# SH06-UI.net
KiCad netlist of a schematic drawn in Altium Designer
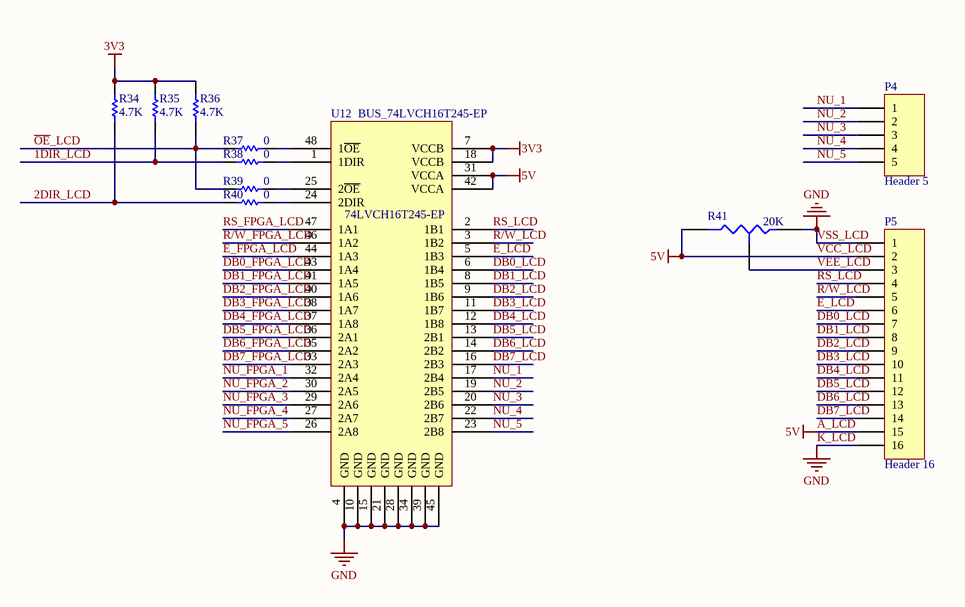
[diagram p0: SH06-UI.SchDoc]

(export (version "E")
  (design (tool "Eeschema 10.0.6"))
  (components
    (comp (ref "P4")
      (value "Header 5")
      (footprint "HDR1X5")
      (description "Header, 5-Pin")
      (fields (field (name "PUBLISHER") "Altium Limited"))
      (libsource (lib "Miscellaneous Connectors") (part "Header 5"))
    )
    (comp (ref "P5")
      (value "Header 16")
      (footprint "HDR1X16")
      (description "Header, 16-Pin")
      (fields (field (name "PUBLISHER") "Altium Limited"))
      (libsource (lib "Miscellaneous Connectors") (part "Header 16"))
    )
    (comp (ref "R34")
      (value "4.7K")
      (footprint "Laser-LiuXin:1608[0603]")
      (description "Resistor")
      (fields (field (name "Comment") "Res,4.7K/0603") (field (name "PUBLISHER") "Altium Limited"))
      (libsource (lib "Miscellaneous Devices") (part "Res1"))
    )
    (comp (ref "R35")
      (value "4.7K")
      (footprint "Laser-LiuXin:1608[0603]")
      (description "Resistor")
      (fields (field (name "Comment") "Res,4.7K/0603") (field (name "PUBLISHER") "Altium Limited"))
      (libsource (lib "Miscellaneous Devices") (part "Res1"))
    )
    (comp (ref "R36")
      (value "4.7K")
      (footprint "Laser-LiuXin:1608[0603]")
      (description "Resistor")
      (fields (field (name "Comment") "Res,4.7K/0603") (field (name "PUBLISHER") "Altium Limited"))
      (libsource (lib "Miscellaneous Devices") (part "Res1"))
    )
    (comp (ref "R37")
      (value "0")
      (footprint "Laser-LiuXin:1608[0603]")
      (description "Resistor")
      (fields (field (name "Comment") "Res,0R/0603") (field (name "PUBLISHER") "Altium Limited"))
      (libsource (lib "Miscellaneous Devices") (part "Res1"))
    )
    (comp (ref "R38")
      (value "0")
      (footprint "Laser-LiuXin:1608[0603]")
      (description "Resistor")
      (fields (field (name "Comment") "Res,0R/0603") (field (name "PUBLISHER") "Altium Limited"))
      (libsource (lib "Miscellaneous Devices") (part "Res1"))
    )
    (comp (ref "R39")
      (value "0")
      (footprint "Laser-LiuXin:1608[0603]")
      (description "Resistor")
      (fields (field (name "Comment") "Res,0R/0603") (field (name "PUBLISHER") "Altium Limited"))
      (libsource (lib "Miscellaneous Devices") (part "Res1"))
    )
    (comp (ref "R40")
      (value "0")
      (footprint "Laser-LiuXin:1608[0603]")
      (description "Resistor")
      (fields (field (name "Comment") "Res,0R/0603") (field (name "PUBLISHER") "Altium Limited"))
      (libsource (lib "Miscellaneous Devices") (part "Res1"))
    )
    (comp (ref "R41")
      (value "20K")
      (footprint "Laser-LiuXin:RES-adj")
      (description "Tapped Resistor")
      (fields (field (name "Comment") "Res Adj,20K") (field (name "PUBLISHER") "Altium Limited"))
      (libsource (lib "Miscellaneous Devices") (part "Res Tap"))
    )
    (comp (ref "U12")
      (value "BUS_74LVCH16T245-EP")
      (footprint "Laser-LiuXin:TSSOP50P810X120-48N")
      (libsource (lib "Laser-LiuXin") (part "BUS_74LVCH16T245-EP"))
    )
  )
  (nets
    (net (code "1") (name "/1DIR_LCD") (class "Default")
      (node (ref "R35") (pin "1") (pinfunction "1_1") (pintype "passive"))
      (node (ref "R38") (pin "1") (pinfunction "1_1") (pintype "passive"))
    )
    (net (code "2") (name "/2DIR_LCD") (class "Default")
      (node (ref "R34") (pin "1") (pinfunction "1_1") (pintype "passive"))
      (node (ref "R40") (pin "1") (pinfunction "1_1") (pintype "passive"))
    )
    (net (code "3") (name "/DB0_FPGA_LCD") (class "Default")
      (node (ref "U12") (pin "43") (pinfunction "1A4_43") (pintype "passive"))
    )
    (net (code "4") (name "/DB0_LCD") (class "Default")
      (node (ref "P5") (pin "7") (pinfunction "7_7") (pintype "passive"))
      (node (ref "U12") (pin "6") (pinfunction "1B4_6") (pintype "passive"))
    )
    (net (code "5") (name "/DB1_FPGA_LCD") (class "Default")
      (node (ref "U12") (pin "41") (pinfunction "1A5_41") (pintype "passive"))
    )
    (net (code "6") (name "/DB1_LCD") (class "Default")
      (node (ref "P5") (pin "8") (pinfunction "8_8") (pintype "passive"))
      (node (ref "U12") (pin "8") (pinfunction "1B5_8") (pintype "passive"))
    )
    (net (code "7") (name "/DB2_FPGA_LCD") (class "Default")
      (node (ref "U12") (pin "40") (pinfunction "1A6_40") (pintype "passive"))
    )
    (net (code "8") (name "/DB2_LCD") (class "Default")
      (node (ref "P5") (pin "9") (pinfunction "9_9") (pintype "passive"))
      (node (ref "U12") (pin "9") (pinfunction "1B6_9") (pintype "passive"))
    )
    (net (code "9") (name "/DB3_FPGA_LCD") (class "Default")
      (node (ref "U12") (pin "38") (pinfunction "1A7_38") (pintype "passive"))
    )
    (net (code "10") (name "/DB3_LCD") (class "Default")
      (node (ref "P5") (pin "10") (pinfunction "10_10") (pintype "passive"))
      (node (ref "U12") (pin "11") (pinfunction "1B7_11") (pintype "passive"))
    )
    (net (code "11") (name "/DB4_FPGA_LCD") (class "Default")
      (node (ref "U12") (pin "37") (pinfunction "1A8_37") (pintype "passive"))
    )
    (net (code "12") (name "/DB4_LCD") (class "Default")
      (node (ref "P5") (pin "11") (pinfunction "11_11") (pintype "passive"))
      (node (ref "U12") (pin "12") (pinfunction "1B8_12") (pintype "passive"))
    )
    (net (code "13") (name "/DB5_FPGA_LCD") (class "Default")
      (node (ref "U12") (pin "36") (pinfunction "2A1_36") (pintype "passive"))
    )
    (net (code "14") (name "/DB5_LCD") (class "Default")
      (node (ref "P5") (pin "12") (pinfunction "12_12") (pintype "passive"))
      (node (ref "U12") (pin "13") (pinfunction "2B1_13") (pintype "passive"))
    )
    (net (code "15") (name "/DB6_FPGA_LCD") (class "Default")
      (node (ref "U12") (pin "35") (pinfunction "2A2_35") (pintype "passive"))
    )
    (net (code "16") (name "/DB6_LCD") (class "Default")
      (node (ref "P5") (pin "13") (pinfunction "13_13") (pintype "passive"))
      (node (ref "U12") (pin "14") (pinfunction "2B2_14") (pintype "passive"))
    )
    (net (code "17") (name "/DB7_FPGA_LCD") (class "Default")
      (node (ref "U12") (pin "33") (pinfunction "2A3_33") (pintype "passive"))
    )
    (net (code "18") (name "/DB7_LCD") (class "Default")
      (node (ref "P5") (pin "14") (pinfunction "14_14") (pintype "passive"))
      (node (ref "U12") (pin "16") (pinfunction "2B3_16") (pintype "passive"))
    )
    (net (code "19") (name "/E_FPGA_LCD") (class "Default")
      (node (ref "U12") (pin "44") (pinfunction "1A3_44") (pintype "passive"))
    )
    (net (code "20") (name "/E_LCD") (class "Default")
      (node (ref "P5") (pin "6") (pinfunction "6_6") (pintype "passive"))
      (node (ref "U12") (pin "5") (pinfunction "1B3_5") (pintype "passive"))
    )
    (net (code "21") (name "/NU_1") (class "Default")
      (node (ref "P4") (pin "1") (pinfunction "1_1") (pintype "passive"))
      (node (ref "U12") (pin "17") (pinfunction "2B4_17") (pintype "passive"))
    )
    (net (code "22") (name "/NU_2") (class "Default")
      (node (ref "P4") (pin "2") (pinfunction "2_2") (pintype "passive"))
      (node (ref "U12") (pin "19") (pinfunction "2B5_19") (pintype "passive"))
    )
    (net (code "23") (name "/NU_3") (class "Default")
      (node (ref "P4") (pin "3") (pinfunction "3_3") (pintype "passive"))
      (node (ref "U12") (pin "20") (pinfunction "2B6_20") (pintype "passive"))
    )
    (net (code "24") (name "/NU_4") (class "Default")
      (node (ref "P4") (pin "4") (pinfunction "4_4") (pintype "passive"))
      (node (ref "U12") (pin "22") (pinfunction "2B7_22") (pintype "passive"))
    )
    (net (code "25") (name "/NU_5") (class "Default")
      (node (ref "P4") (pin "5") (pinfunction "5_5") (pintype "passive"))
      (node (ref "U12") (pin "23") (pinfunction "2B8_23") (pintype "passive"))
    )
    (net (code "26") (name "/NU_FPGA_1") (class "Default")
      (node (ref "U12") (pin "32") (pinfunction "2A4_32") (pintype "passive"))
    )
    (net (code "27") (name "/NU_FPGA_2") (class "Default")
      (node (ref "U12") (pin "30") (pinfunction "2A5_30") (pintype "passive"))
    )
    (net (code "28") (name "/NU_FPGA_3") (class "Default")
      (node (ref "U12") (pin "29") (pinfunction "2A6_29") (pintype "passive"))
    )
    (net (code "29") (name "/NU_FPGA_4") (class "Default")
      (node (ref "U12") (pin "27") (pinfunction "2A7_27") (pintype "passive"))
    )
    (net (code "30") (name "/NU_FPGA_5") (class "Default")
      (node (ref "U12") (pin "26") (pinfunction "2A8_26") (pintype "passive"))
    )
    (net (code "31") (name "/RS_FPGA_LCD") (class "Default")
      (node (ref "U12") (pin "47") (pinfunction "1A1_47") (pintype "passive"))
    )
    (net (code "32") (name "/RS_LCD") (class "Default")
      (node (ref "P5") (pin "4") (pinfunction "4_4") (pintype "passive"))
      (node (ref "U12") (pin "2") (pinfunction "1B1_2") (pintype "passive"))
    )
    (net (code "33") (name "/R{slash}W_FPGA_LCD") (class "Default")
      (node (ref "U12") (pin "46") (pinfunction "1A2_46") (pintype "passive"))
    )
    (net (code "34") (name "/R{slash}W_LCD") (class "Default")
      (node (ref "P5") (pin "5") (pinfunction "5_5") (pintype "passive"))
      (node (ref "U12") (pin "3") (pinfunction "1B2_3") (pintype "passive"))
    )
    (net (code "35") (name "/VEE_LCD") (class "Default")
      (node (ref "P5") (pin "3") (pinfunction "3_3") (pintype "passive"))
      (node (ref "R41") (pin "3") (pinfunction "TAP_3") (pintype "passive"))
    )
    (net (code "36") (name "/~{OE}_LCD") (class "Default")
      (node (ref "R36") (pin "1") (pinfunction "1_1") (pintype "passive"))
      (node (ref "R37") (pin "1") (pinfunction "1_1") (pintype "passive"))
      (node (ref "R39") (pin "1") (pinfunction "1_1") (pintype "passive"))
    )
    (net (code "37") (name "3V3") (class "Default")
      (node (ref "R34") (pin "2") (pinfunction "2_2") (pintype "passive"))
      (node (ref "R35") (pin "2") (pinfunction "2_2") (pintype "passive"))
      (node (ref "R36") (pin "2") (pinfunction "2_2") (pintype "passive"))
      (node (ref "U12") (pin "18") (pinfunction "VCCB_18") (pintype "passive"))
      (node (ref "U12") (pin "7") (pinfunction "VCCB_7") (pintype "passive"))
    )
    (net (code "38") (name "5V") (class "Default")
      (node (ref "P5") (pin "15") (pinfunction "15_15") (pintype "passive"))
      (node (ref "P5") (pin "2") (pinfunction "2_2") (pintype "passive"))
      (node (ref "R41") (pin "2") (pinfunction "B_2") (pintype "passive"))
      (node (ref "U12") (pin "31") (pinfunction "VCCA_31") (pintype "passive"))
      (node (ref "U12") (pin "42") (pinfunction "VCCA_42") (pintype "passive"))
    )
    (net (code "39") (name "GND") (class "Default")
      (node (ref "P5") (pin "1") (pinfunction "1_1") (pintype "passive"))
      (node (ref "P5") (pin "16") (pinfunction "16_16") (pintype "passive"))
      (node (ref "R41") (pin "1") (pinfunction "A_1") (pintype "passive"))
      (node (ref "U12") (pin "10") (pinfunction "GND_10") (pintype "passive"))
      (node (ref "U12") (pin "15") (pinfunction "GND_15") (pintype "passive"))
      (node (ref "U12") (pin "21") (pinfunction "GND_21") (pintype "passive"))
      (node (ref "U12") (pin "28") (pinfunction "GND_28") (pintype "passive"))
      (node (ref "U12") (pin "34") (pinfunction "GND_34") (pintype "passive"))
      (node (ref "U12") (pin "39") (pinfunction "GND_39") (pintype "passive"))
      (node (ref "U12") (pin "4") (pinfunction "GND_4") (pintype "passive"))
      (node (ref "U12") (pin "45") (pinfunction "GND_45") (pintype "passive"))
    )
    (net (code "40") (name "Net-(U12-1DIR)") (class "Default")
      (node (ref "R38") (pin "2") (pinfunction "2_2") (pintype "passive"))
      (node (ref "U12") (pin "1") (pinfunction "1DIR_1") (pintype "passive"))
    )
    (net (code "41") (name "Net-(U12-1~{OE})") (class "Default")
      (node (ref "R37") (pin "2") (pinfunction "2_2") (pintype "passive"))
      (node (ref "U12") (pin "48") (pinfunction "1~{OE}_48") (pintype "passive"))
    )
    (net (code "42") (name "Net-(U12-2DIR)") (class "Default")
      (node (ref "R40") (pin "2") (pinfunction "2_2") (pintype "passive"))
      (node (ref "U12") (pin "24") (pinfunction "2DIR_24") (pintype "passive"))
    )
    (net (code "43") (name "Net-(U12-2~{OE})") (class "Default")
      (node (ref "R39") (pin "2") (pinfunction "2_2") (pintype "passive"))
      (node (ref "U12") (pin "25") (pinfunction "2~{OE}_25") (pintype "passive"))
    )
  )
)
